# ESP_SensorThing.net
KiCad netlist of a schematic drawn in EAGLE
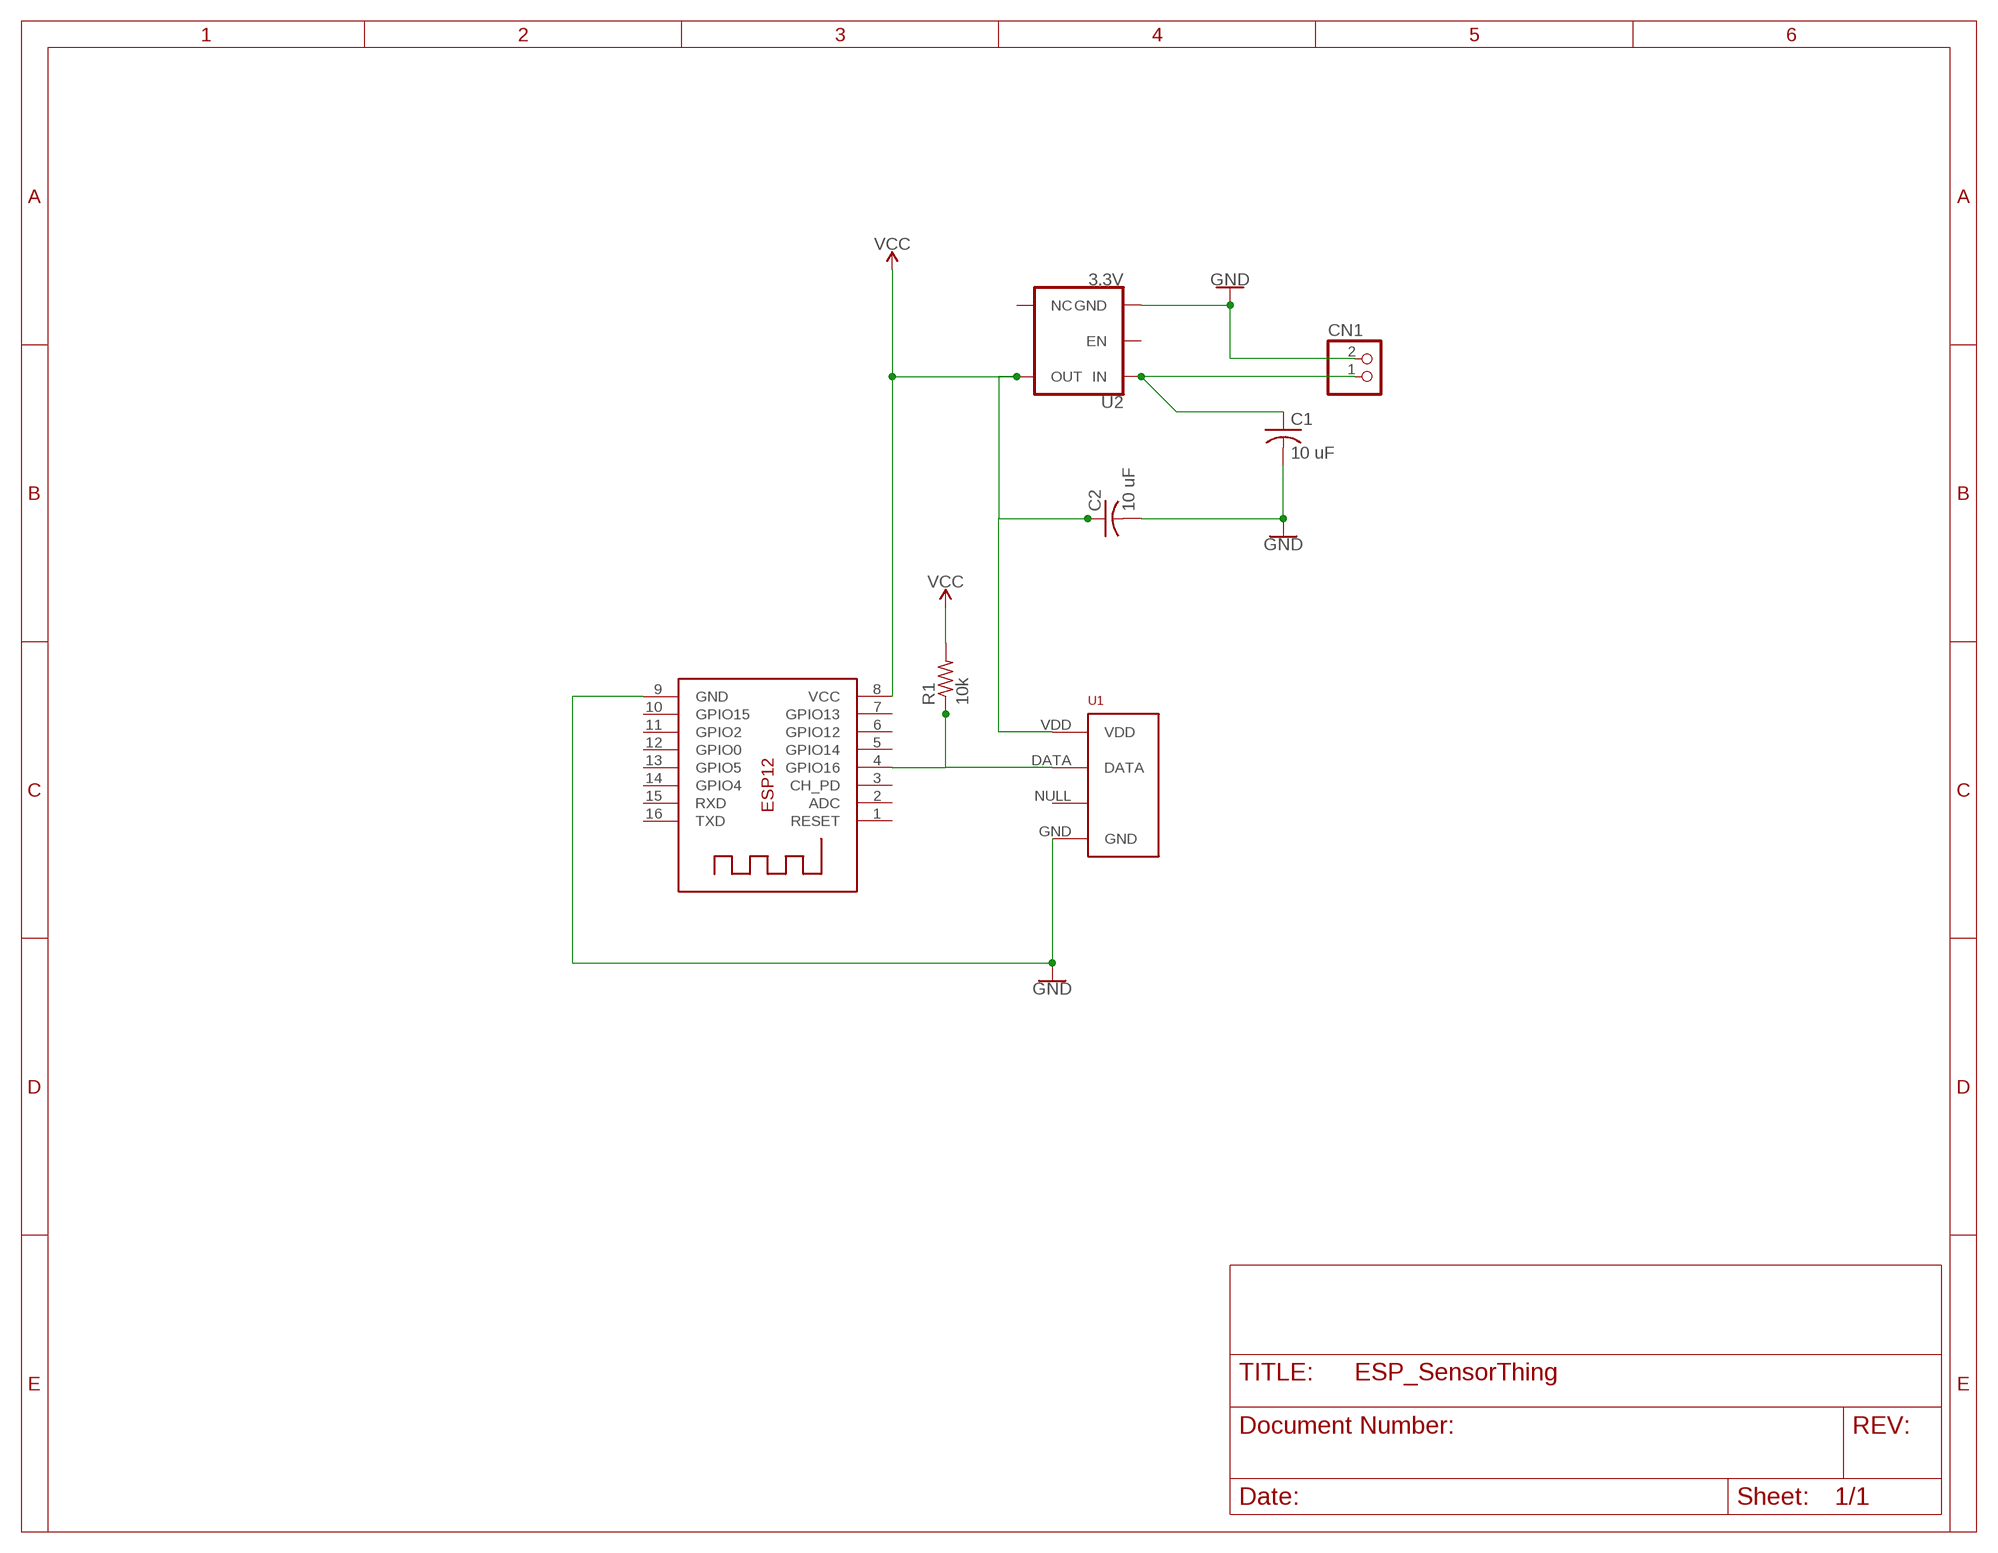
[diagram p0: schematic, sheet 1]

(export (version "E")
  (design (tool "Eeschema 10.0.6"))
  (components
    (comp (ref "C1")
      (value "10 uF")
      (footprint "eagle-import:C1210")
      (libsource (lib "eagle-import") (part "C-USC1210"))
    )
    (comp (ref "C2")
      (value "10 uF")
      (footprint "eagle-import:C1210")
      (libsource (lib "eagle-import") (part "C-USC1210"))
    )
    (comp (ref "CN1")
      (value "JST_2PIN-SMT-RA")
      (footprint "eagle-import:JST-PH-2-SMT-RA")
      (libsource (lib "eagle-import") (part "JST_2PIN-SMT-RA"))
    )
    (comp (ref "R1")
      (value "10k")
      (footprint "eagle-import:R0805")
      (libsource (lib "eagle-import") (part "R-US_R0805"))
    )
    (comp (ref "U1")
      (value "RHT03_DHT-22_AM2302RA")
      (footprint "eagle-import:RHT03_DHT-22_RA")
      (libsource (lib "eagle-import") (part "RHT03_DHT-22_AM2302RA"))
    )
    (comp (ref "U2")
      (value "3.3V")
      (footprint "eagle-import:SOT23-5")
      (libsource (lib "eagle-import") (part "V_REG_AP2112K-3.3V"))
    )
    (comp (ref "X1")
      (value "ESP-12")
      (footprint "eagle-import:ESP-12")
      (libsource (lib "eagle-import") (part "ESP-12"))
    )
  )
  (nets
    (net (code "1") (name "GND") (class "Default")
      (node (ref "C1") (pin "2") (pinfunction "2_2") (pintype "passive"))
      (node (ref "C2") (pin "2") (pinfunction "2_2") (pintype "passive"))
      (node (ref "CN1") (pin "2") (pinfunction "1_2") (pintype "passive"))
      (node (ref "U1") (pin "GND") (pinfunction "GND_GND") (pintype "power_in"))
      (node (ref "U2") (pin "2") (pinfunction "GND_2") (pintype "input"))
      (node (ref "X1") (pin "9") (pinfunction "GND_9") (pintype "power_in"))
    )
    (net (code "2") (name "Net-(CN1-2)") (class "Default")
      (node (ref "C1") (pin "1") (pinfunction "1_1") (pintype "passive"))
      (node (ref "CN1") (pin "1") (pinfunction "2_1") (pintype "passive"))
      (node (ref "U2") (pin "1") (pinfunction "IN_1") (pintype "input"))
    )
    (net (code "3") (name "Net-(X1-GPIO16)") (class "Default")
      (node (ref "R1") (pin "1") (pinfunction "1_1") (pintype "passive"))
      (node (ref "U1") (pin "DATA") (pinfunction "DATA_DATA") (pintype "bidirectional"))
      (node (ref "X1") (pin "4") (pinfunction "GPIO16_4") (pintype "bidirectional"))
    )
    (net (code "4") (name "VCC") (class "Default")
      (node (ref "C2") (pin "1") (pinfunction "1_1") (pintype "passive"))
      (node (ref "R1") (pin "2") (pinfunction "2_2") (pintype "passive"))
      (node (ref "U1") (pin "VDD") (pinfunction "VDD_VDD") (pintype "power_in"))
      (node (ref "U2") (pin "5") (pinfunction "OUT_5") (pintype "passive"))
      (node (ref "X1") (pin "8") (pinfunction "VCC_8") (pintype "power_in"))
    )
    (net (code "5") (name "unconnected-(U1-PadNULL)") (class "Default")
      (node (ref "U1") (pin "NULL") (pinfunction "NULL_NULL") (pintype "no_connect"))
    )
    (net (code "6") (name "unconnected-(U2-EN-Pad3)") (class "Default")
      (node (ref "U2") (pin "3") (pinfunction "EN_3") (pintype "input"))
    )
    (net (code "7") (name "unconnected-(U2-NC-Pad4)") (class "Default")
      (node (ref "U2") (pin "4") (pinfunction "NC_4") (pintype "no_connect"))
    )
    (net (code "8") (name "unconnected-(X1-ADC-Pad2)") (class "Default")
      (node (ref "X1") (pin "2") (pinfunction "ADC_2") (pintype "passive"))
    )
    (net (code "9") (name "unconnected-(X1-CH_PD-Pad3)") (class "Default")
      (node (ref "X1") (pin "3") (pinfunction "CH_PD_3") (pintype "input"))
    )
    (net (code "10") (name "unconnected-(X1-GPIO0-Pad12)") (class "Default")
      (node (ref "X1") (pin "12") (pinfunction "GPIO0_12") (pintype "bidirectional"))
    )
    (net (code "11") (name "unconnected-(X1-GPIO2-Pad11)") (class "Default")
      (node (ref "X1") (pin "11") (pinfunction "GPIO2_11") (pintype "bidirectional"))
    )
    (net (code "12") (name "unconnected-(X1-GPIO4-Pad14)") (class "Default")
      (node (ref "X1") (pin "14") (pinfunction "GPIO4_14") (pintype "bidirectional"))
    )
    (net (code "13") (name "unconnected-(X1-GPIO5-Pad13)") (class "Default")
      (node (ref "X1") (pin "13") (pinfunction "GPIO5_13") (pintype "bidirectional"))
    )
    (net (code "14") (name "unconnected-(X1-GPIO12-Pad6)") (class "Default")
      (node (ref "X1") (pin "6") (pinfunction "GPIO12_6") (pintype "bidirectional"))
    )
    (net (code "15") (name "unconnected-(X1-GPIO13-Pad7)") (class "Default")
      (node (ref "X1") (pin "7") (pinfunction "GPIO13_7") (pintype "bidirectional"))
    )
    (net (code "16") (name "unconnected-(X1-GPIO14-Pad5)") (class "Default")
      (node (ref "X1") (pin "5") (pinfunction "GPIO14_5") (pintype "bidirectional"))
    )
    (net (code "17") (name "unconnected-(X1-GPIO15-Pad10)") (class "Default")
      (node (ref "X1") (pin "10") (pinfunction "GPIO15_10") (pintype "bidirectional"))
    )
    (net (code "18") (name "unconnected-(X1-RESET-Pad1)") (class "Default")
      (node (ref "X1") (pin "1") (pinfunction "RESET_1") (pintype "input"))
    )
    (net (code "19") (name "unconnected-(X1-RXD-Pad15)") (class "Default")
      (node (ref "X1") (pin "15") (pinfunction "RXD_15") (pintype "input"))
    )
    (net (code "20") (name "unconnected-(X1-TXD-Pad16)") (class "Default")
      (node (ref "X1") (pin "16") (pinfunction "TXD_16") (pintype "output"))
    )
  )
)
